# USB_Connector.net
KiCad netlist of a schematic drawn in Altium Designer
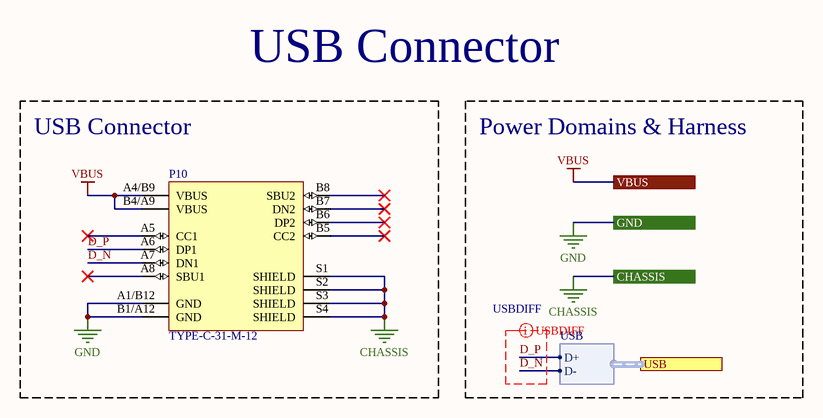
[diagram p0: USB_Connector.SchDoc]

(export (version "E")
  (design (tool "Eeschema 10.0.6"))
  (components
    (comp (ref "P10")
      (value "TYPE-C-31-M-12")
      (footprint "TYPE-C-31-M-12")
      (description "USB C SMD Connector")
      (fields
        (field (name "MANUFACTURER") "Korean Hroparts Elec")
        (field (name "MANUFACTURER PART NUMBER") "TYPE-C-31-M-12")
      )
      (libsource (lib "Library") (part "TYPE-C-31-M-12"))
    )
  )
  (nets
    (net (code "2") (name "/D_N") (class "Default")
      (node (ref "P10") (pin "A7") (pinfunction "DN1_A7") (pintype "bidirectional"))
    )
    (net (code "3") (name "/D_P") (class "Default")
      (node (ref "P10") (pin "A6") (pinfunction "DP1_A6") (pintype "bidirectional"))
    )
    (net (code "5") (name "CHASSIS") (class "Default")
      (node (ref "P10") (pin "S1") (pinfunction "SHIELD_S1") (pintype "passive"))
      (node (ref "P10") (pin "S2") (pinfunction "SHIELD_S2") (pintype "passive"))
      (node (ref "P10") (pin "S3") (pinfunction "SHIELD_S3") (pintype "passive"))
      (node (ref "P10") (pin "S4") (pinfunction "SHIELD_S4") (pintype "passive"))
    )
    (net (code "6") (name "GND") (class "Default")
      (node (ref "P10") (pin "A1/B12") (pinfunction "GND_A1/B12") (pintype "power_in"))
      (node (ref "P10") (pin "B1/A12") (pinfunction "GND_B1/A12") (pintype "power_in"))
    )
    (net (code "7") (name "VBUS") (class "Default")
      (node (ref "P10") (pin "A4/B9") (pinfunction "VBUS_A4/B9") (pintype "power_in"))
      (node (ref "P10") (pin "B4/A9") (pinfunction "VBUS_B4/A9") (pintype "power_in"))
    )
    (net (code "8") (name "unconnected-(P10-CC1-PadA5)") (class "Default")
      (node (ref "P10") (pin "A5") (pinfunction "CC1_A5") (pintype "bidirectional+no_connect"))
    )
    (net (code "9") (name "unconnected-(P10-CC2-PadB5)") (class "Default")
      (node (ref "P10") (pin "B5") (pinfunction "CC2_B5") (pintype "bidirectional+no_connect"))
    )
    (net (code "10") (name "unconnected-(P10-DN2-PadB7)") (class "Default")
      (node (ref "P10") (pin "B7") (pinfunction "DN2_B7") (pintype "bidirectional+no_connect"))
    )
    (net (code "11") (name "unconnected-(P10-DP2-PadB6)") (class "Default")
      (node (ref "P10") (pin "B6") (pinfunction "DP2_B6") (pintype "bidirectional+no_connect"))
    )
    (net (code "12") (name "unconnected-(P10-SBU1-PadA8)") (class "Default")
      (node (ref "P10") (pin "A8") (pinfunction "SBU1_A8") (pintype "bidirectional+no_connect"))
    )
    (net (code "13") (name "unconnected-(P10-SBU2-PadB8)") (class "Default")
      (node (ref "P10") (pin "B8") (pinfunction "SBU2_B8") (pintype "bidirectional+no_connect"))
    )
  )
)
